# source_eagle.net
KiCad netlist of a schematic drawn in EAGLE
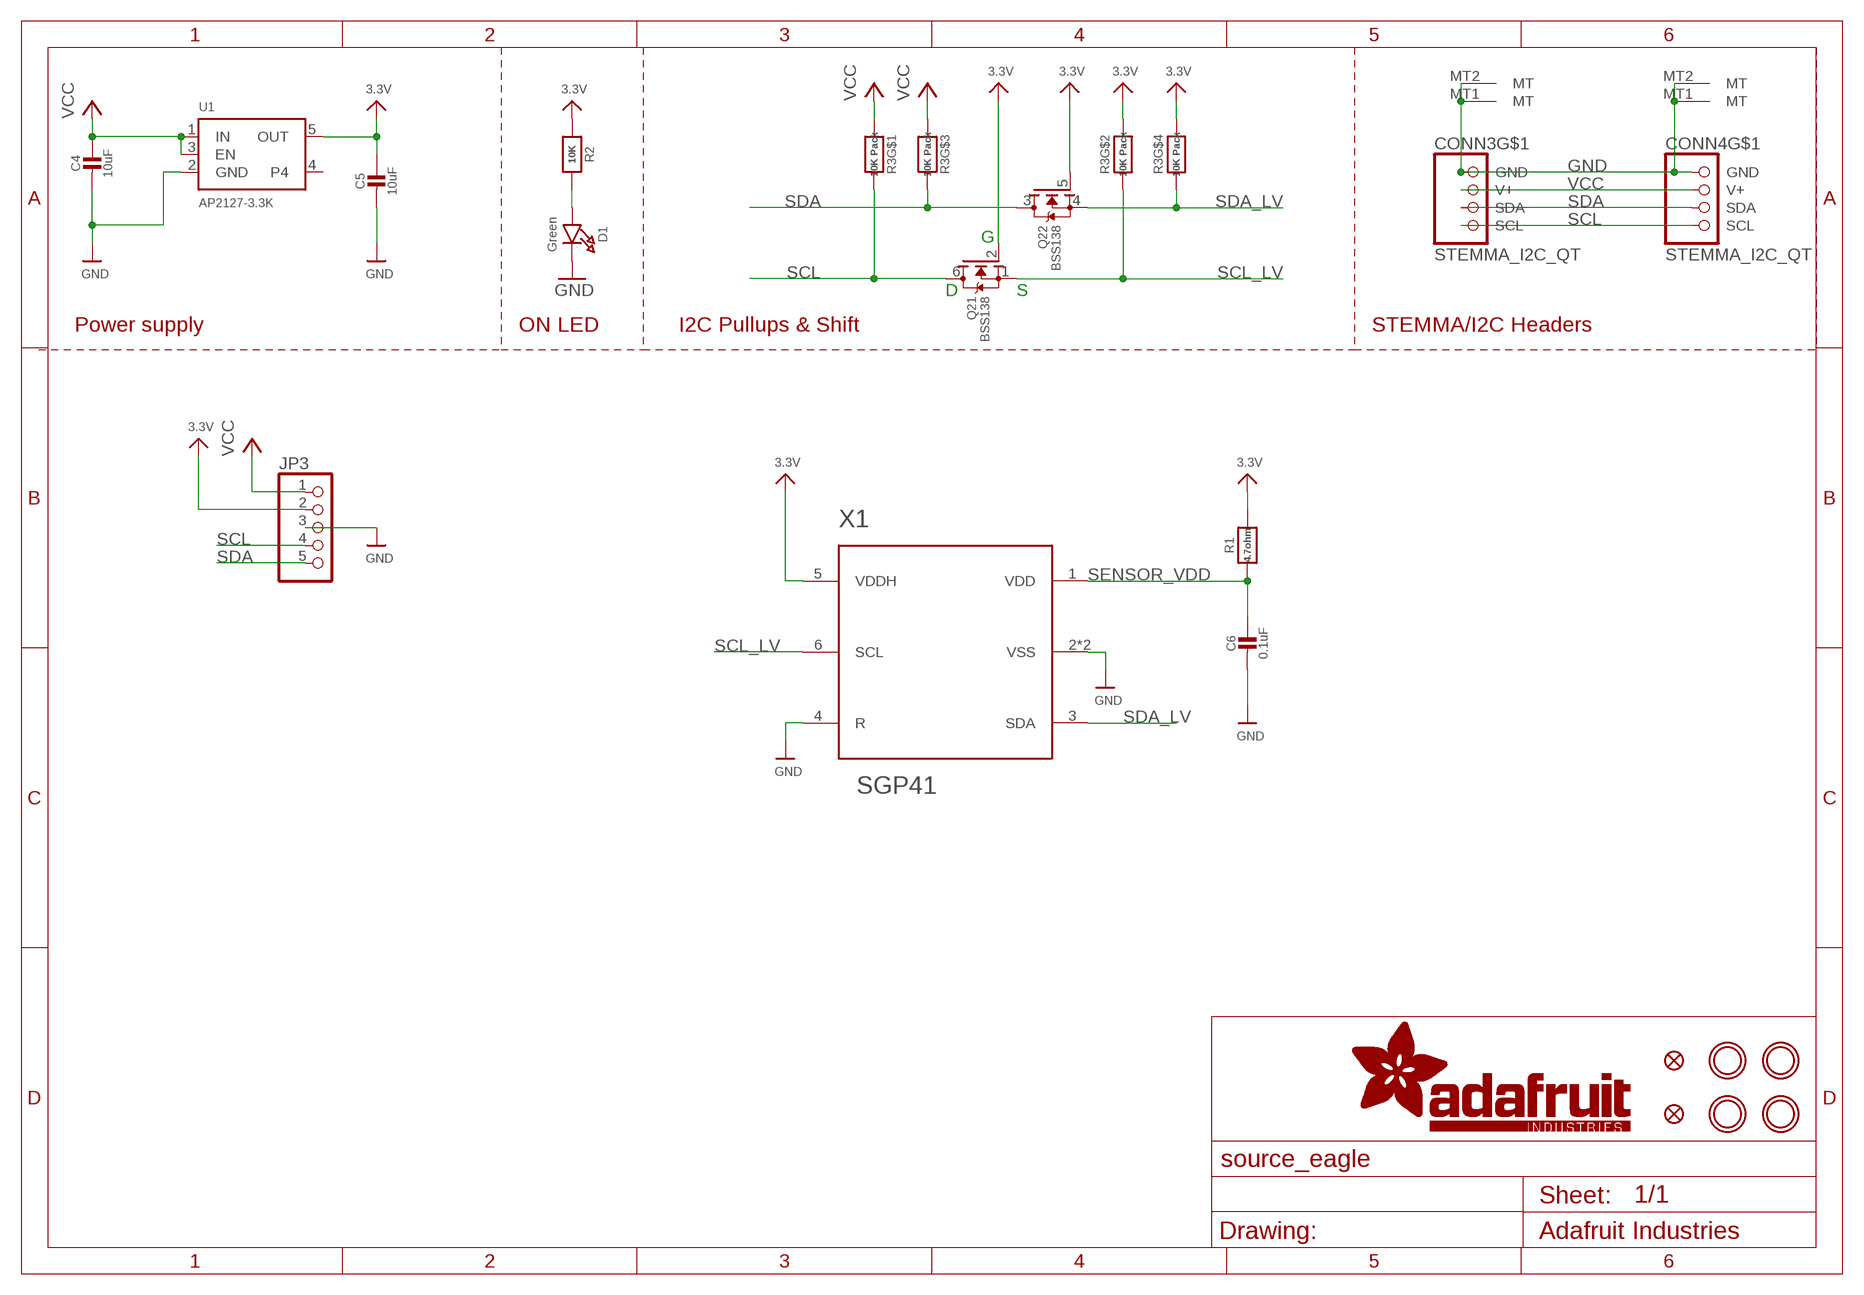
[diagram p0: schematic, sheet 1]

(export (version "E")
  (design (tool "Eeschema 10.0.6"))
  (components
    (comp (ref "C4")
      (value "10uF")
      (footprint "eagle-import:0805-NO")
      (libsource (lib "eagle-import") (part "CAP_CERAMIC0805-NOOUTLINE"))
    )
    (comp (ref "C5")
      (value "10uF")
      (footprint "eagle-import:0805-NO")
      (libsource (lib "eagle-import") (part "CAP_CERAMIC0805-NOOUTLINE"))
    )
    (comp (ref "C6")
      (value "0.1uF")
      (footprint "eagle-import:0603-NO")
      (libsource (lib "eagle-import") (part "CAP_CERAMIC0603_NO"))
    )
    (comp (ref "CONN3")
      (value "STEMMA_I2C_QT")
      (footprint "eagle-import:JST_SH4")
      (libsource (lib "eagle-import") (part "STEMMA_I2C_QT"))
    )
    (comp (ref "CONN4")
      (value "STEMMA_I2C_QT")
      (footprint "eagle-import:JST_SH4")
      (libsource (lib "eagle-import") (part "STEMMA_I2C_QT"))
    )
    (comp (ref "D1")
      (value "Green")
      (footprint "eagle-import:CHIPLED_0603_NOOUTLINE")
      (libsource (lib "eagle-import") (part "LED0603_NOOUTLINE"))
    )
    (comp (ref "FID3")
      (value "FIDUCIAL_1MM")
      (footprint "eagle-import:FIDUCIAL_1MM")
      (libsource (lib "eagle-import") (part "FIDUCIAL_1MM"))
    )
    (comp (ref "FID4")
      (value "FIDUCIAL_1MM")
      (footprint "eagle-import:FIDUCIAL_1MM")
      (libsource (lib "eagle-import") (part "FIDUCIAL_1MM"))
    )
    (comp (ref "JP3")
      (value "HEADER-1X570MIL")
      (footprint "eagle-import:1X05_ROUND_70")
      (libsource (lib "eagle-import") (part "HEADER-1X570MIL"))
    )
    (comp (ref "Q2")
      (value "BSS138")
      (footprint "eagle-import:SOT363")
      (libsource (lib "eagle-import") (part "MOSFET-N_DUAL"))
    )
    (comp (ref "R1")
      (value "4.7ohm")
      (footprint "eagle-import:0603-NO")
      (libsource (lib "eagle-import") (part "RESISTOR_0603_NOOUT"))
    )
    (comp (ref "R2")
      (value "10K")
      (footprint "eagle-import:0603-NO")
      (libsource (lib "eagle-import") (part "RESISTOR_0603_NOOUT"))
    )
    (comp (ref "R3")
      (value "10K Pack")
      (footprint "eagle-import:RESPACK_4X0603")
      (libsource (lib "eagle-import") (part "RESISTOR_4PACK"))
    )
    (comp (ref "U$28")
      (value "MOUNTINGHOLE2.5")
      (footprint "eagle-import:MOUNTINGHOLE_2.5_PLATED")
      (libsource (lib "eagle-import") (part "MOUNTINGHOLE2.5"))
    )
    (comp (ref "U$29")
      (value "MOUNTINGHOLE2.5")
      (footprint "eagle-import:MOUNTINGHOLE_2.5_PLATED")
      (libsource (lib "eagle-import") (part "MOUNTINGHOLE2.5"))
    )
    (comp (ref "U$31")
      (value "MOUNTINGHOLE2.5")
      (footprint "eagle-import:MOUNTINGHOLE_2.5_PLATED")
      (libsource (lib "eagle-import") (part "MOUNTINGHOLE2.5"))
    )
    (comp (ref "U$32")
      (value "MOUNTINGHOLE2.5")
      (footprint "eagle-import:MOUNTINGHOLE_2.5_PLATED")
      (libsource (lib "eagle-import") (part "MOUNTINGHOLE2.5"))
    )
    (comp (ref "U1")
      (value "AP2127-3.3K")
      (footprint "eagle-import:SOT23-5")
      (libsource (lib "eagle-import") (part "VREG_SOT23-5"))
    )
    (comp (ref "X1")
      (value "SGP41")
      (footprint "eagle-import:SGP30")
      (libsource (lib "eagle-import") (part "SGP30"))
    )
  )
  (nets
    (net (code "1") (name "/SCL") (class "Default")
      (node (ref "CONN3") (pin "4") (pinfunction "SCL_4") (pintype "passive"))
      (node (ref "CONN4") (pin "4") (pinfunction "SCL_4") (pintype "passive"))
      (node (ref "JP3") (pin "4") (pinfunction "4_4") (pintype "passive"))
      (node (ref "Q2") (pin "6") (pinfunction "D_6") (pintype "bidirectional"))
      (node (ref "R3") (pin "8") (pinfunction "2_8") (pintype "passive"))
    )
    (net (code "2") (name "/SCL_LV") (class "Default")
      (node (ref "Q2") (pin "1") (pinfunction "S_1") (pintype "bidirectional"))
      (node (ref "R3") (pin "7") (pinfunction "2_7") (pintype "passive"))
      (node (ref "X1") (pin "6") (pinfunction "SCL_6") (pintype "bidirectional"))
    )
    (net (code "3") (name "/SDA") (class "Default")
      (node (ref "CONN3") (pin "3") (pinfunction "SDA_3") (pintype "passive"))
      (node (ref "CONN4") (pin "3") (pinfunction "SDA_3") (pintype "passive"))
      (node (ref "JP3") (pin "5") (pinfunction "5_5") (pintype "passive"))
      (node (ref "Q2") (pin "3") (pinfunction "D_3") (pintype "bidirectional"))
      (node (ref "R3") (pin "6") (pinfunction "2_6") (pintype "passive"))
    )
    (net (code "4") (name "/SDA_LV") (class "Default")
      (node (ref "Q2") (pin "4") (pinfunction "S_4") (pintype "bidirectional"))
      (node (ref "R3") (pin "5") (pinfunction "2_5") (pintype "passive"))
      (node (ref "X1") (pin "3") (pinfunction "SDA_3") (pintype "bidirectional"))
    )
    (net (code "5") (name "/SENSOR_VDD") (class "Default")
      (node (ref "C6") (pin "1") (pinfunction "1_1") (pintype "passive"))
      (node (ref "R1") (pin "1") (pinfunction "1_1") (pintype "passive"))
      (node (ref "X1") (pin "1") (pinfunction "VDD_1") (pintype "bidirectional"))
    )
    (net (code "6") (name "3.3V") (class "Default")
      (node (ref "C5") (pin "1") (pinfunction "1_1") (pintype "passive"))
      (node (ref "JP3") (pin "2") (pinfunction "2_2") (pintype "passive"))
      (node (ref "Q2") (pin "2") (pinfunction "G_2") (pintype "bidirectional"))
      (node (ref "Q2") (pin "5") (pinfunction "G_5") (pintype "bidirectional"))
      (node (ref "R1") (pin "2") (pinfunction "2_2") (pintype "passive"))
      (node (ref "R2") (pin "1") (pinfunction "1_1") (pintype "passive"))
      (node (ref "R3") (pin "2") (pinfunction "1_2") (pintype "passive"))
      (node (ref "R3") (pin "4") (pinfunction "1_4") (pintype "passive"))
      (node (ref "U1") (pin "5") (pinfunction "OUT_5") (pintype "power_in"))
      (node (ref "X1") (pin "5") (pinfunction "VDDH_5") (pintype "bidirectional"))
    )
    (net (code "7") (name "GND") (class "Default")
      (node (ref "C4") (pin "2") (pinfunction "2_2") (pintype "passive"))
      (node (ref "C5") (pin "2") (pinfunction "2_2") (pintype "passive"))
      (node (ref "C6") (pin "2") (pinfunction "2_2") (pintype "passive"))
      (node (ref "CONN3") (pin "1") (pinfunction "GND_1") (pintype "passive"))
      (node (ref "CONN3") (pin "MT1") (pinfunction "MT_MT1") (pintype "bidirectional"))
      (node (ref "CONN3") (pin "MT2") (pinfunction "MT_MT2") (pintype "bidirectional"))
      (node (ref "CONN4") (pin "1") (pinfunction "GND_1") (pintype "passive"))
      (node (ref "CONN4") (pin "MT1") (pinfunction "MT_MT1") (pintype "bidirectional"))
      (node (ref "CONN4") (pin "MT2") (pinfunction "MT_MT2") (pintype "bidirectional"))
      (node (ref "D1") (pin "C") (pinfunction "C_C") (pintype "passive"))
      (node (ref "JP3") (pin "3") (pinfunction "3_3") (pintype "passive"))
      (node (ref "U1") (pin "2") (pinfunction "GND_2") (pintype "power_in"))
      (node (ref "X1") (pin "2") (pinfunction "VSS_2") (pintype "bidirectional"))
      (node (ref "X1") (pin "4") (pinfunction "R_4") (pintype "bidirectional"))
      (node (ref "X1") (pin "P$7") (pinfunction "VSS_P$7") (pintype "bidirectional"))
    )
    (net (code "8") (name "Net-(D1-PadA)") (class "Default")
      (node (ref "D1") (pin "A") (pinfunction "A_A") (pintype "passive"))
      (node (ref "R2") (pin "2") (pinfunction "2_2") (pintype "passive"))
    )
    (net (code "9") (name "VCC") (class "Default")
      (node (ref "C4") (pin "1") (pinfunction "1_1") (pintype "passive"))
      (node (ref "CONN3") (pin "2") (pinfunction "V+_2") (pintype "passive"))
      (node (ref "CONN4") (pin "2") (pinfunction "V+_2") (pintype "passive"))
      (node (ref "JP3") (pin "1") (pinfunction "1_1") (pintype "passive"))
      (node (ref "R3") (pin "1") (pinfunction "1_1") (pintype "passive"))
      (node (ref "R3") (pin "3") (pinfunction "1_3") (pintype "passive"))
      (node (ref "U1") (pin "1") (pinfunction "IN_1") (pintype "power_in"))
      (node (ref "U1") (pin "3") (pinfunction "EN_3") (pintype "input"))
    )
    (net (code "10") (name "unconnected-(U1-P4-Pad4)") (class "Default")
      (node (ref "U1") (pin "4") (pinfunction "P4_4") (pintype "bidirectional"))
    )
  )
)
